# Sheet1.net
KiCad netlist of a schematic drawn in Altium Designer
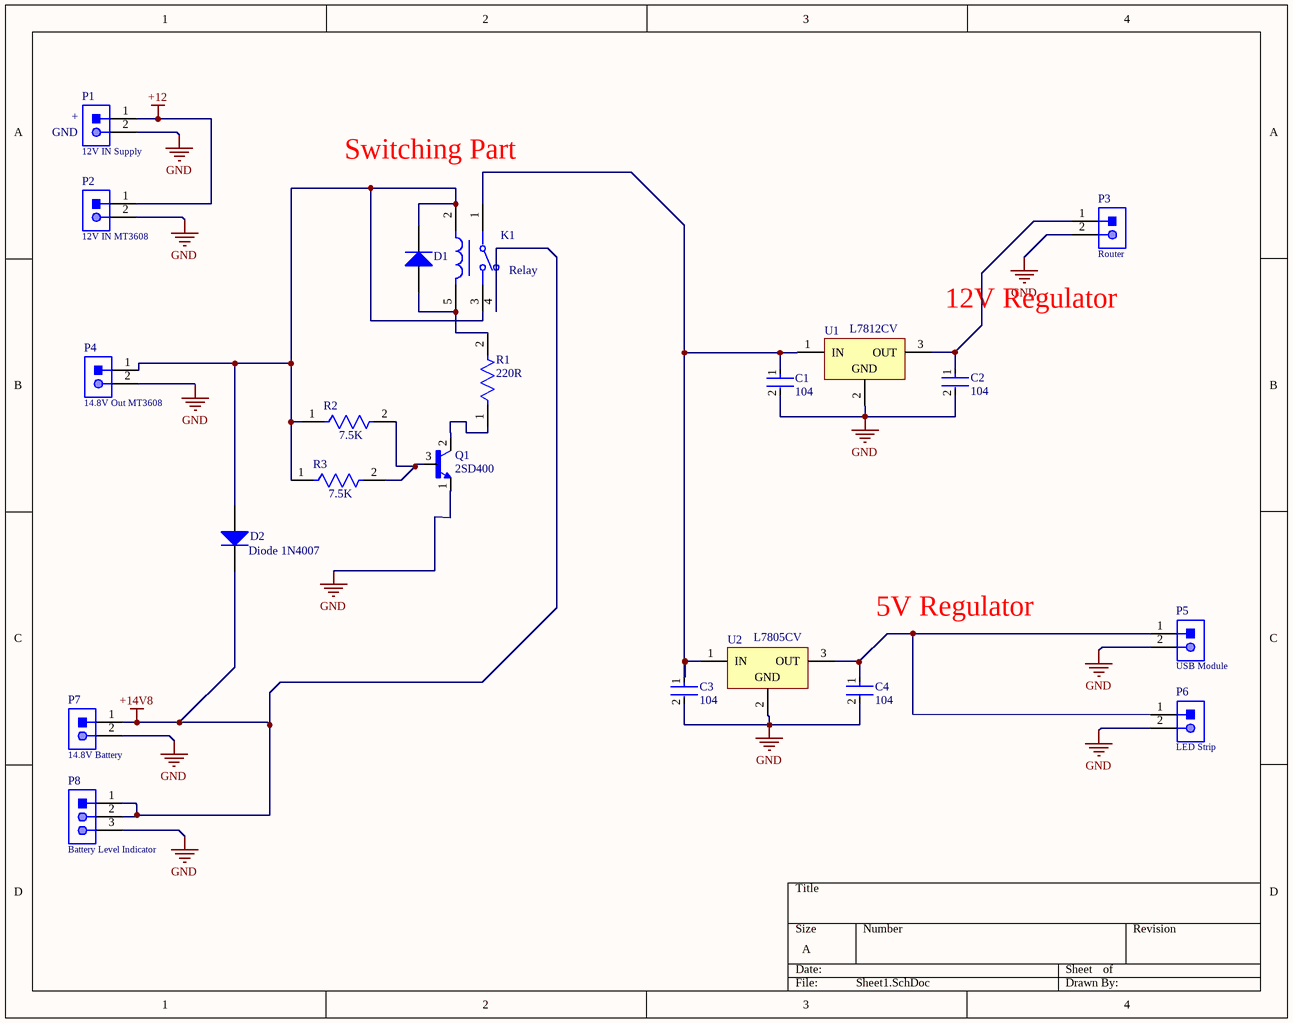
[diagram p0: Sheet1.SchDoc]

(export (version "E")
  (design (tool "Eeschema 10.0.6"))
  (components
    (comp (ref "C1")
      (value "104")
      (footprint "FP-RCE0K1-MFG")
      (description "Cap Ceramic 1pF 100V C0G ±0.25pF Radial 5mm +125°C Automotive Bulk")
      (libsource (lib "Altium Content Vault") (part "b4654b650e69147ec39a6b967a45e02"))
    )
    (comp (ref "C2")
      (value "104")
      (footprint "FP-RCE0K1-MFG")
      (description "Cap Ceramic 1pF 100V C0G ±0.25pF Radial 5mm +125°C Automotive Bulk")
      (libsource (lib "Altium Content Vault") (part "b4654b650e69147ec39a6b967a45e02"))
    )
    (comp (ref "C3")
      (value "104")
      (footprint "FP-RCE0K1-MFG")
      (description "Cap Ceramic 1pF 100V C0G ±0.25pF Radial 5mm +125°C Automotive Bulk")
      (libsource (lib "Altium Content Vault") (part "b4654b650e69147ec39a6b967a45e02"))
    )
    (comp (ref "C4")
      (value "104")
      (footprint "FP-RCE0K1-MFG")
      (description "Cap Ceramic 1pF 100V C0G ±0.25pF Radial 5mm +125°C Automotive Bulk")
      (libsource (lib "Altium Content Vault") (part "b4654b650e69147ec39a6b967a45e02"))
    )
    (comp (ref "D1")
      (value "Diode 1N4001")
      (footprint "DO-41")
      (description "1 Amp General Purpose Rectifier")
      (fields (field (name "PUBLISHER") "Altium Limited"))
      (libsource (lib "Miscellaneous Devices") (part "Diode 1N4001"))
    )
    (comp (ref "D2")
      (value "Diode 1N4007")
      (footprint "DO-41")
      (description "1 Amp General Purpose Rectifier")
      (fields (field (name "PUBLISHER") "Altium Limited"))
      (libsource (lib "Miscellaneous Devices") (part "Diode 1N4007"))
    )
    (comp (ref "K1")
      (value "Relay")
      (footprint "FP-JS1-5V-F-MFG")
      (description "RELAY GEN PURPOSE SPDT 10A 5V")
      (fields
        (field (name "MANUFACTURER PART NUMBER") "JS1-5V-F")
        (field (name "OCTOPART") "https://octopart.com/js1-5v-f-panasonic-39428621")
      )
      (libsource (lib "Altium Content Vault") (part "250623531296f86beaf95f2bc4a6d4c"))
    )
    (comp (ref "P1")
      (value "12V IN Supply")
      (footprint "61300211121")
      (description "THT Vertical Pin Header WR-PHD, Pitch 2.54 mm, Single Row, 2 pins")
      (fields
        (field (name "MANUFACTURER") "Wurth Elektronik")
        (field (name "PART NUMBER") "61300211121")
        (field (name "PUBLISHER") "WurthElektronik")
      )
      (libsource (lib "Altium Content Vault") (part "WE-CN-1P-M-R2"))
    )
    (comp (ref "P2")
      (value "12V IN MT3608")
      (footprint "61300211121")
      (description "THT Vertical Pin Header WR-PHD, Pitch 2.54 mm, Single Row, 2 pins")
      (fields
        (field (name "MANUFACTURER") "Wurth Elektronik")
        (field (name "PART NUMBER") "61300211121")
        (field (name "PUBLISHER") "WurthElektronik")
      )
      (libsource (lib "Altium Content Vault") (part "WE-CN-1P-M-R2"))
    )
    (comp (ref "P3")
      (value "Router")
      (footprint "61300211121")
      (description "THT Vertical Pin Header WR-PHD, Pitch 2.54 mm, Single Row, 2 pins")
      (fields
        (field (name "MANUFACTURER") "Wurth Elektronik")
        (field (name "PART NUMBER") "61300211121")
        (field (name "PUBLISHER") "WurthElektronik")
      )
      (libsource (lib "") (part "WE-CN-1P-M-R2_1"))
    )
    (comp (ref "P4")
      (value "14.8V Out MT3608")
      (footprint "61300211121")
      (description "THT Vertical Pin Header WR-PHD, Pitch 2.54 mm, Single Row, 2 pins")
      (fields
        (field (name "MANUFACTURER") "Wurth Elektronik")
        (field (name "PART NUMBER") "61300211121")
        (field (name "PUBLISHER") "WurthElektronik")
      )
      (libsource (lib "Altium Content Vault") (part "WE-CN-1P-M-R2"))
    )
    (comp (ref "P5")
      (value "USB Module")
      (footprint "61300211121")
      (description "THT Vertical Pin Header WR-PHD, Pitch 2.54 mm, Single Row, 2 pins")
      (fields
        (field (name "MANUFACTURER") "Wurth Elektronik")
        (field (name "PART NUMBER") "61300211121")
        (field (name "PUBLISHER") "WurthElektronik")
      )
      (libsource (lib "") (part "WE-CN-1P-M-R2_1"))
    )
    (comp (ref "P6")
      (value "LED Strip")
      (footprint "61300211121")
      (description "THT Vertical Pin Header WR-PHD, Pitch 2.54 mm, Single Row, 2 pins")
      (fields
        (field (name "MANUFACTURER") "Wurth Elektronik")
        (field (name "PART NUMBER") "61300211121")
        (field (name "PUBLISHER") "WurthElektronik")
      )
      (libsource (lib "") (part "WE-CN-1P-M-R2_1"))
    )
    (comp (ref "P7")
      (value "14.8V Battery")
      (footprint "61300211121")
      (description "THT Vertical Pin Header WR-PHD, Pitch 2.54 mm, Single Row, 2 pins")
      (fields
        (field (name "MANUFACTURER") "Wurth Elektronik")
        (field (name "PART NUMBER") "61300211121")
        (field (name "PUBLISHER") "WurthElektronik")
      )
      (libsource (lib "Altium Content Vault") (part "WE-CN-1P-M-R2"))
    )
    (comp (ref "P8")
      (value "Battery Level Indicator")
      (footprint "61900319521")
      (description "Male Top Locking Header WR-WTB, THT, Right Angled, pitch 2.54 mm, 1 x 3 position")
      (fields
        (field (name "PART NUMBER") "61900319521")
        (field (name "MANUFACTURER") "Wurth Elektronik")
        (field (name "PUBLISHER") "WurthElektronik")
      )
      (libsource (lib "Altium Content Vault") (part "WE-CN-1P-M-R3"))
    )
    (comp (ref "Q1")
      (value "2SD400")
      (footprint "TO145P470X600X850-3P")
      (description "Connector Header Through Hole 20 position 0.100 _2.54mm_")
      (fields (field (name "MF") "Samtec Inc."))
      (libsource (lib "SnapEDAsch") (part "2SD400"))
    )
    (comp (ref "R1")
      (value "PCF14JT7K50")
      (footprint "FP-CF14-MFG")
      (description "RES 7.5K OHM 1/4W 5% AXIAL")
      (fields (field (name "RESISTANCE") "220R") (field (name "TOLERANCE") "5%"))
      (libsource (lib "Altium Content Vault") (part "1029c3af85768c4190bb7ad29bc67b5"))
    )
    (comp (ref "R2")
      (value "PCF14JT7K50")
      (footprint "FP-CF14-MFG")
      (description "RES 7.5K OHM 1/4W 5% AXIAL")
      (fields (field (name "RESISTANCE") "7.5K") (field (name "TOLERANCE") "5%"))
      (libsource (lib "Altium Content Vault") (part "1029c3af85768c4190bb7ad29bc67b5"))
    )
    (comp (ref "R3")
      (value "PCF14JT7K50")
      (footprint "FP-CF14-MFG")
      (description "RES 7.5K OHM 1/4W 5% AXIAL")
      (fields (field (name "RESISTANCE") "7.5K") (field (name "TOLERANCE") "5%"))
      (libsource (lib "Altium Content Vault") (part "1029c3af85768c4190bb7ad29bc67b5"))
    )
    (comp (ref "U1")
      (value "L7812CV")
      (footprint "TO220")
      (description "Positive Voltage Regulator, 12V, 3-Pin TO-220")
      (libsource (lib "Altium Content Vault") (part "PM-REG-L4940-SIL3"))
    )
    (comp (ref "U2")
      (value "L7805CV")
      (footprint "TO220")
      (description "Positive Voltage Regulator, 5V, 3-Pin TO-220")
      (libsource (lib "Altium Content Vault") (part "PM-REG-L4940-SIL3"))
    )
  )
  (nets
    (net (code "1") (name "+12") (class "Default")
      (node (ref "P1") (pin "1") (pinfunction "1_1") (pintype "passive"))
      (node (ref "P2") (pin "1") (pinfunction "1_1") (pintype "passive"))
    )
    (net (code "2") (name "+14V8") (class "Default")
      (node (ref "D2") (pin "2") (pinfunction "K_2") (pintype "passive"))
      (node (ref "K1") (pin "4") (pinfunction "N.C._4") (pintype "passive"))
      (node (ref "P7") (pin "1") (pinfunction "1_1") (pintype "passive"))
      (node (ref "P8") (pin "1") (pinfunction "1_1") (pintype "passive"))
      (node (ref "P8") (pin "2") (pinfunction "2_2") (pintype "passive"))
    )
    (net (code "3") (name "GND") (class "Default")
      (node (ref "C1") (pin "2") (pinfunction "2_2") (pintype "passive"))
      (node (ref "C2") (pin "2") (pinfunction "2_2") (pintype "passive"))
      (node (ref "C3") (pin "2") (pinfunction "2_2") (pintype "passive"))
      (node (ref "C4") (pin "2") (pinfunction "2_2") (pintype "passive"))
      (node (ref "P1") (pin "2") (pinfunction "2_2") (pintype "passive"))
      (node (ref "P2") (pin "2") (pinfunction "2_2") (pintype "passive"))
      (node (ref "P3") (pin "2") (pinfunction "2_2") (pintype "passive"))
      (node (ref "P4") (pin "2") (pinfunction "2_2") (pintype "passive"))
      (node (ref "P5") (pin "2") (pinfunction "2_2") (pintype "passive"))
      (node (ref "P6") (pin "2") (pinfunction "2_2") (pintype "passive"))
      (node (ref "P7") (pin "2") (pinfunction "2_2") (pintype "passive"))
      (node (ref "P8") (pin "3") (pinfunction "3_3") (pintype "passive"))
      (node (ref "Q1") (pin "1") (pinfunction "E_1") (pintype "passive"))
      (node (ref "U1") (pin "2") (pinfunction "GND_2") (pintype "power_in"))
      (node (ref "U2") (pin "2") (pinfunction "GND_2") (pintype "power_in"))
    )
    (net (code "4") (name "Net-(D1-A)") (class "Default")
      (node (ref "D1") (pin "1") (pinfunction "A_1") (pintype "passive"))
      (node (ref "K1") (pin "5") (pinfunction "2_COIL_5") (pintype "passive"))
      (node (ref "R1") (pin "2") (pinfunction "2_2") (pintype "passive"))
    )
    (net (code "5") (name "Net-(D1-K)") (class "Default")
      (node (ref "D1") (pin "2") (pinfunction "K_2") (pintype "passive"))
      (node (ref "D2") (pin "1") (pinfunction "A_1") (pintype "passive"))
      (node (ref "K1") (pin "2") (pinfunction "1_COIL_2") (pintype "passive"))
      (node (ref "K1") (pin "3") (pinfunction "N.O._3") (pintype "passive"))
      (node (ref "P4") (pin "1") (pinfunction "1_1") (pintype "passive"))
      (node (ref "R2") (pin "1") (pinfunction "1_1") (pintype "passive"))
      (node (ref "R3") (pin "1") (pinfunction "1_1") (pintype "passive"))
    )
    (net (code "6") (name "Net-(K1-COM)") (class "Default")
      (node (ref "C1") (pin "1") (pinfunction "1_1") (pintype "passive"))
      (node (ref "C3") (pin "1") (pinfunction "1_1") (pintype "passive"))
      (node (ref "K1") (pin "1") (pinfunction "COM_1") (pintype "passive"))
      (node (ref "U1") (pin "1") (pinfunction "IN_1") (pintype "power_in"))
      (node (ref "U2") (pin "1") (pinfunction "IN_1") (pintype "power_in"))
    )
    (net (code "7") (name "Net-(Q1-B)") (class "Default")
      (node (ref "Q1") (pin "3") (pinfunction "B_3") (pintype "passive"))
      (node (ref "R2") (pin "2") (pinfunction "2_2") (pintype "passive"))
      (node (ref "R3") (pin "2") (pinfunction "2_2") (pintype "passive"))
    )
    (net (code "8") (name "Net-(Q1-C)") (class "Default")
      (node (ref "Q1") (pin "2") (pinfunction "C_2") (pintype "passive"))
      (node (ref "R1") (pin "1") (pinfunction "1_1") (pintype "passive"))
    )
    (net (code "9") (name "Net-(U1-OUT)") (class "Default")
      (node (ref "C2") (pin "1") (pinfunction "1_1") (pintype "passive"))
      (node (ref "P3") (pin "1") (pinfunction "1_1") (pintype "passive"))
      (node (ref "U1") (pin "3") (pinfunction "OUT_3") (pintype "power_in"))
    )
    (net (code "10") (name "Net-(U2-OUT)") (class "Default")
      (node (ref "C4") (pin "1") (pinfunction "1_1") (pintype "passive"))
      (node (ref "P5") (pin "1") (pinfunction "1_1") (pintype "passive"))
      (node (ref "P6") (pin "1") (pinfunction "1_1") (pintype "passive"))
      (node (ref "U2") (pin "3") (pinfunction "OUT_3") (pintype "power_in"))
    )
  )
)
